# extensionboard.net
KiCad netlist of a schematic drawn in Altium Designer
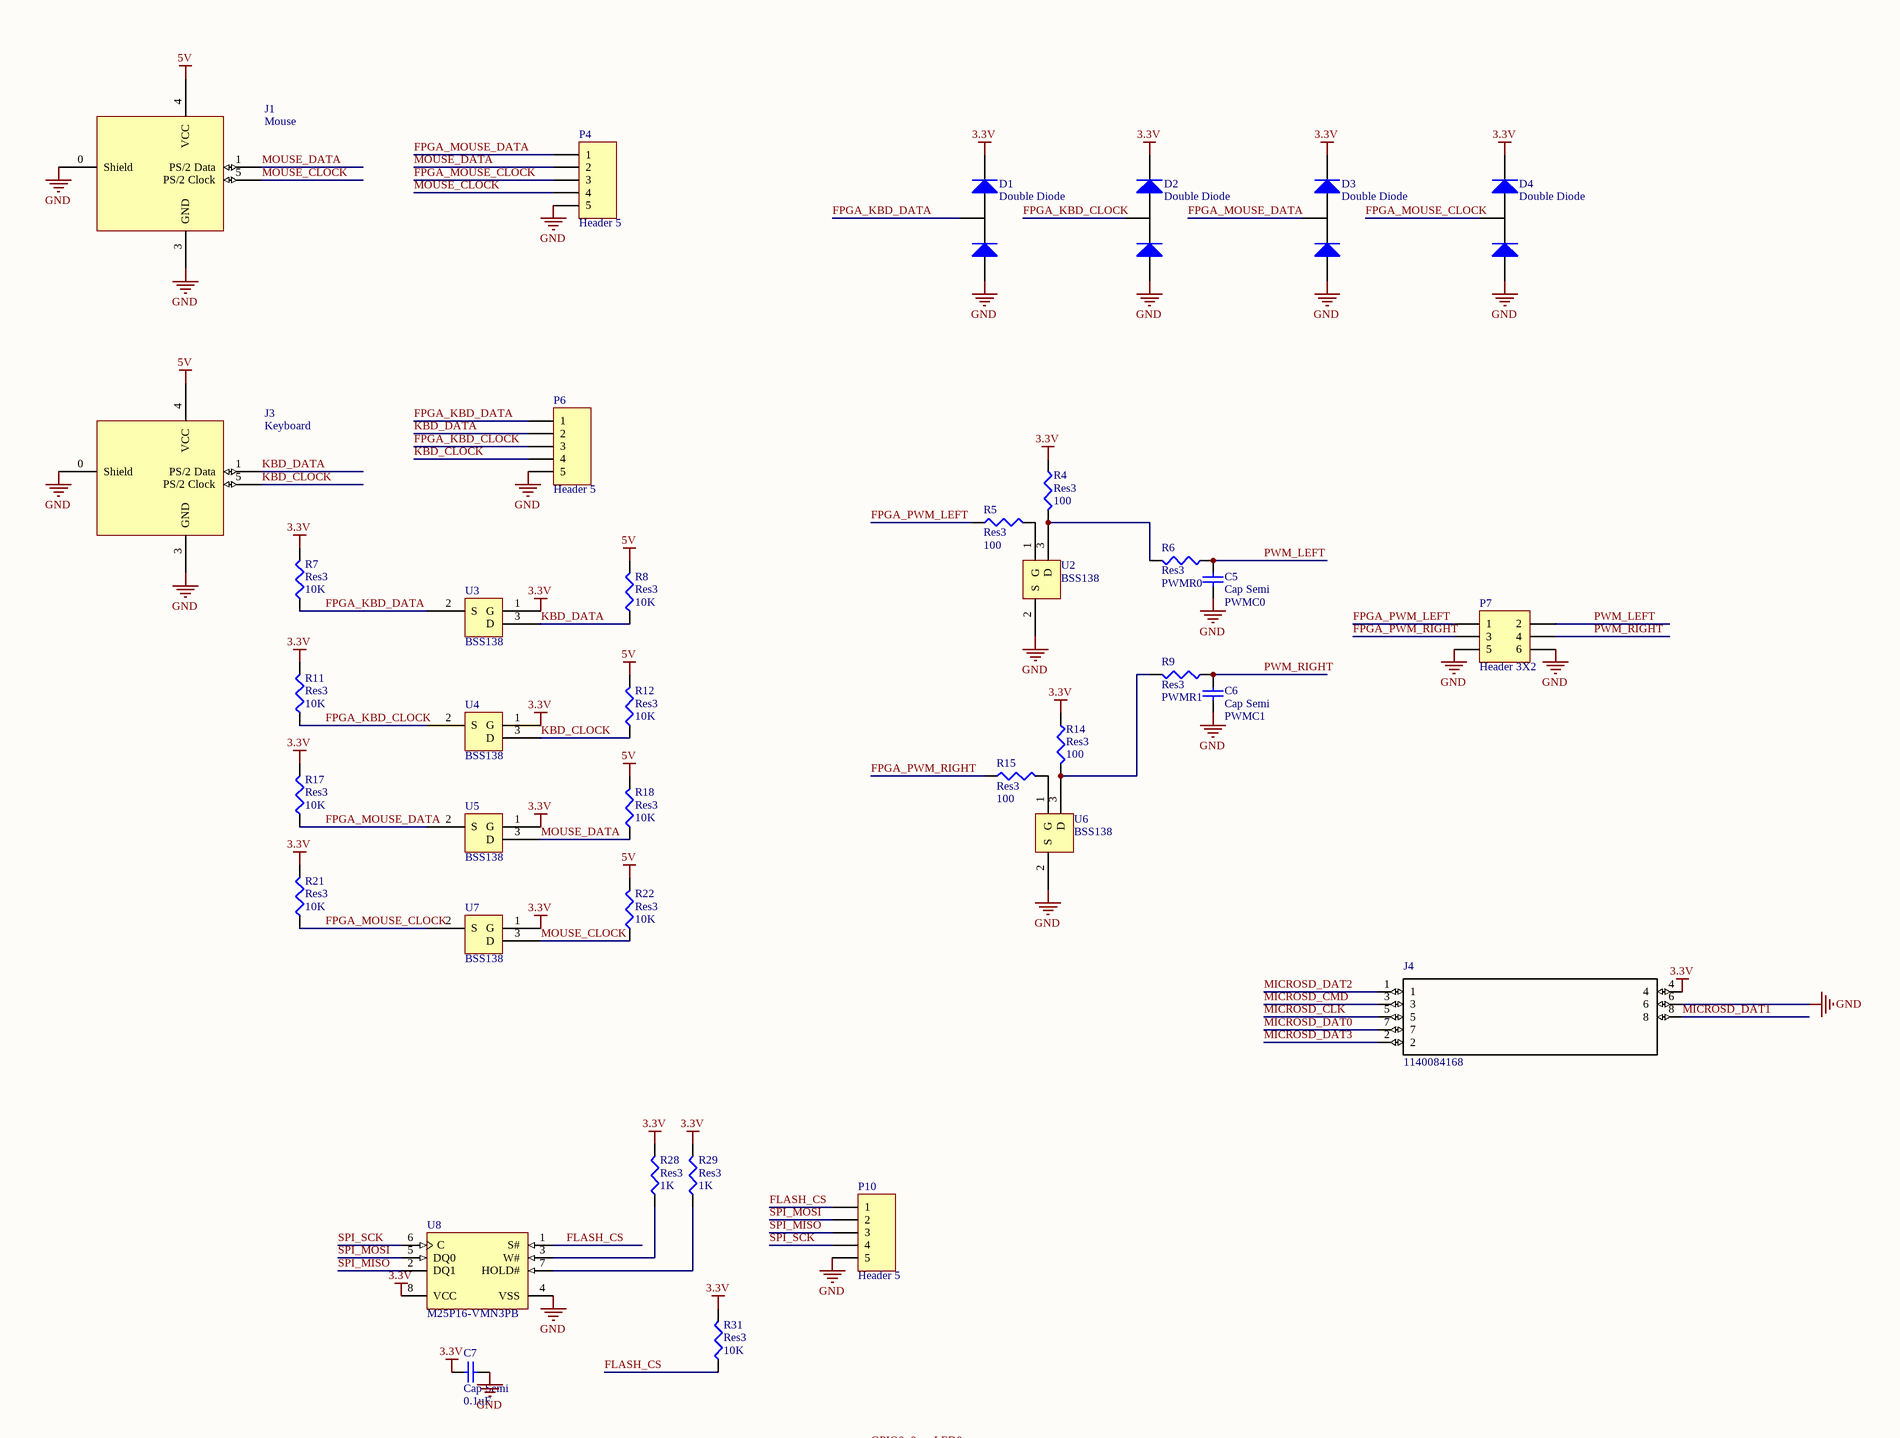
[diagram p0: extensionboard.SchDoc, top left]
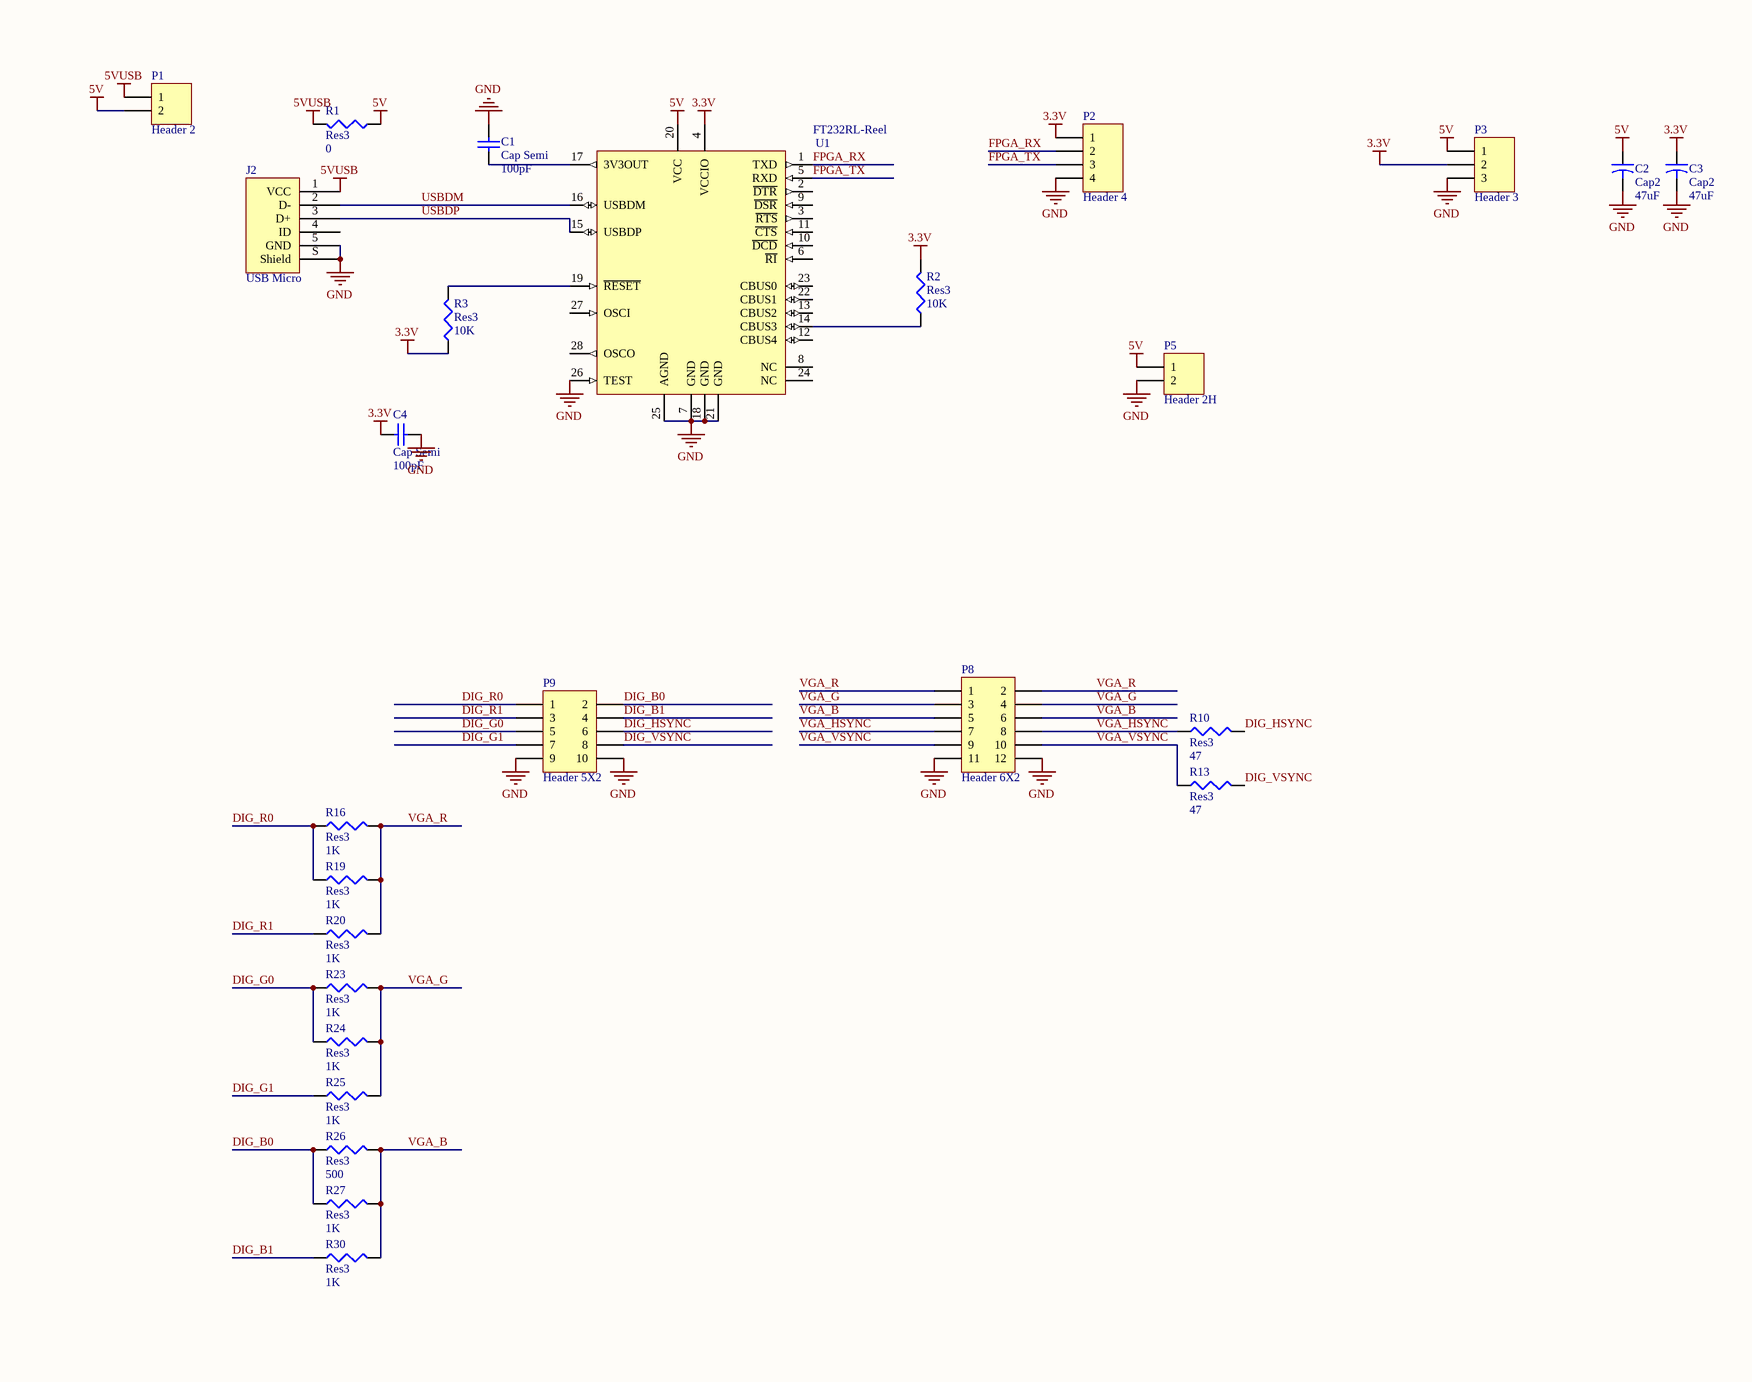
[diagram p1: extensionboard.SchDoc, top right]
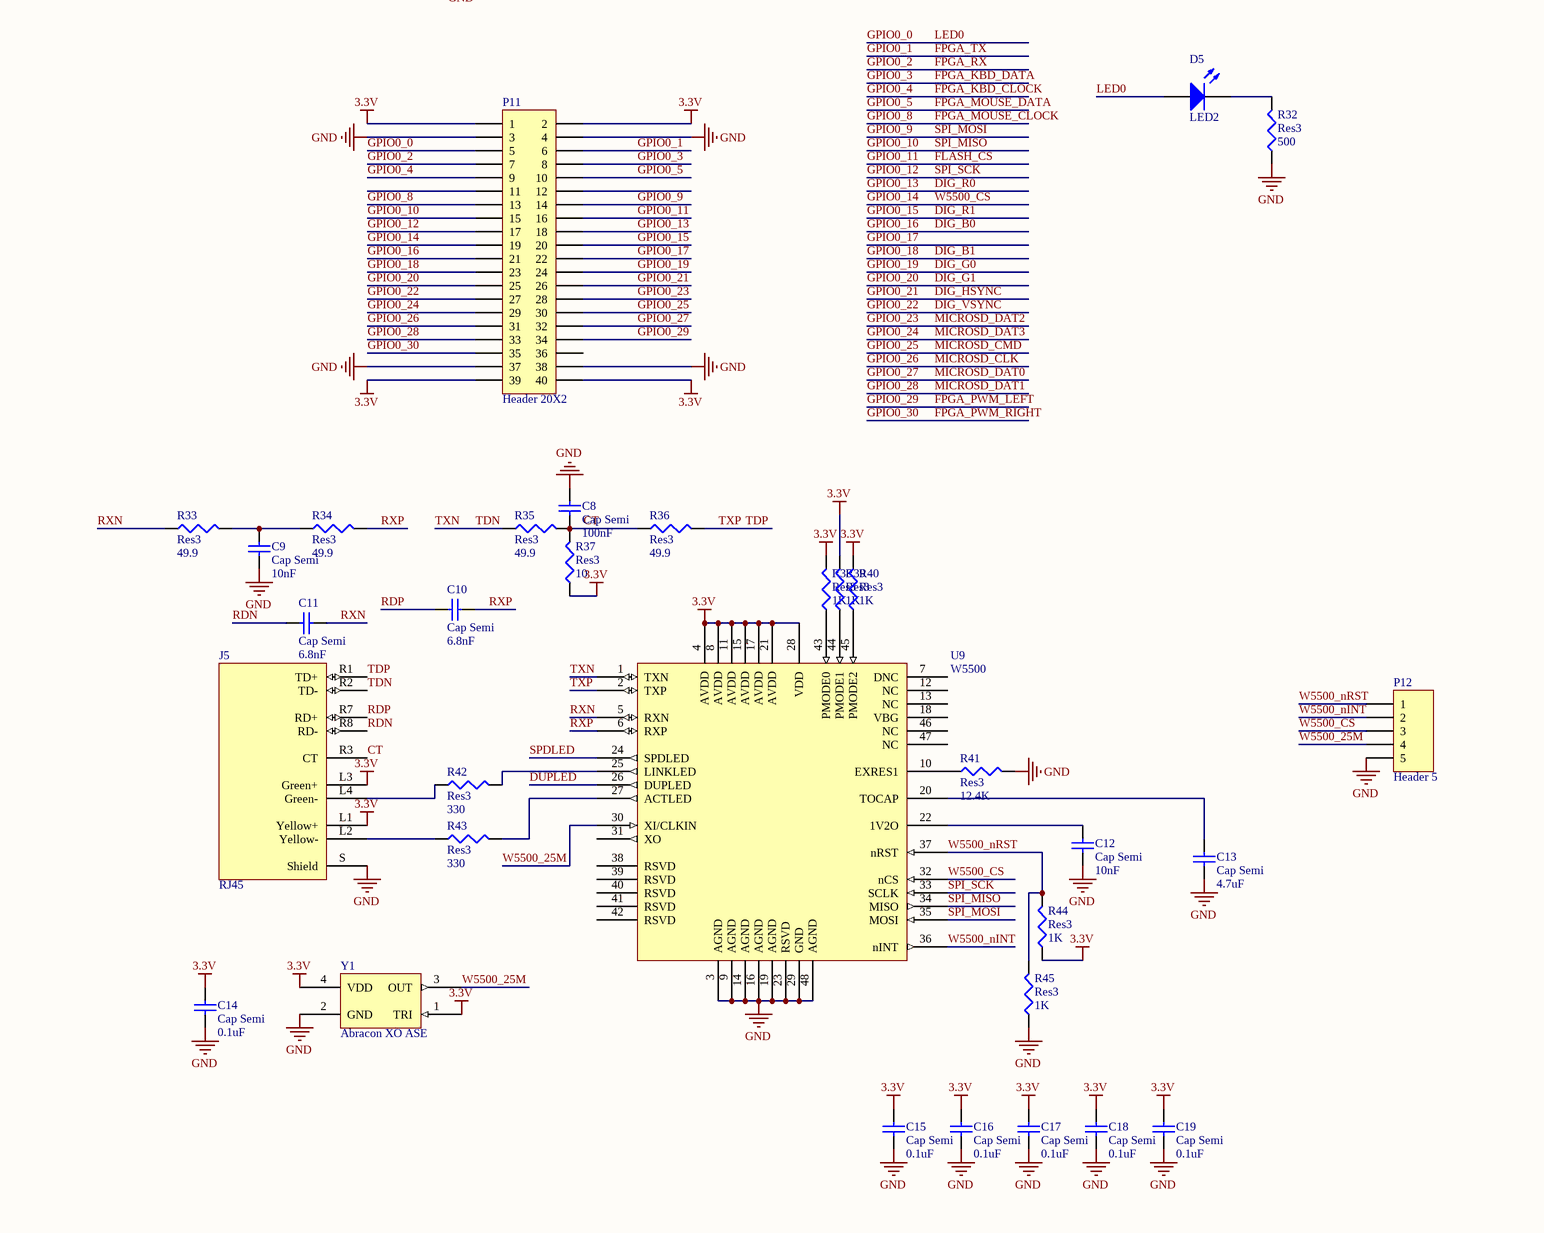
[diagram p2: extensionboard.SchDoc, bottom left]

(export (version "E")
  (design (tool "Eeschema 10.0.6"))
  (components
    (comp (ref "C1")
      (value "Cap Semi")
      (footprint "1608[0603]")
      (description "Capacitor (Semiconductor SIM Model)")
      (fields (field (name "ALTIUM_VALUE") "100pF") (field (name "PUBLISHER") "Altium Limited"))
      (libsource (lib "Miscellaneous Devices") (part "Cap Semi"))
    )
    (comp (ref "C2")
      (value "Cap2")
      (footprint "CAPR5-4X5")
      (description "Capacitor")
      (fields (field (name "ALTIUM_VALUE") "47uF") (field (name "PUBLISHER") "Altium Limited"))
      (libsource (lib "Miscellaneous Devices") (part "Cap2"))
    )
    (comp (ref "C3")
      (value "Cap2")
      (footprint "CAPR5-4X5")
      (description "Capacitor")
      (fields (field (name "ALTIUM_VALUE") "47uF") (field (name "PUBLISHER") "Altium Limited"))
      (libsource (lib "Miscellaneous Devices") (part "Cap2"))
    )
    (comp (ref "C4")
      (value "Cap Semi")
      (footprint "1608[0603]")
      (description "Capacitor (Semiconductor SIM Model)")
      (fields (field (name "ALTIUM_VALUE") "100pF") (field (name "PUBLISHER") "Altium Limited"))
      (libsource (lib "Miscellaneous Devices") (part "Cap Semi"))
    )
    (comp (ref "C5")
      (value "Cap Semi")
      (footprint "C1210")
      (description "Capacitor (Semiconductor SIM Model)")
      (fields (field (name "ALTIUM_VALUE") "PWMC0") (field (name "PUBLISHER") "Altium Limited"))
      (libsource (lib "Miscellaneous Devices") (part "Cap Semi"))
    )
    (comp (ref "C6")
      (value "Cap Semi")
      (footprint "C1210")
      (description "Capacitor (Semiconductor SIM Model)")
      (fields (field (name "ALTIUM_VALUE") "PWMC1") (field (name "PUBLISHER") "Altium Limited"))
      (libsource (lib "Miscellaneous Devices") (part "Cap Semi"))
    )
    (comp (ref "C7")
      (value "Cap Semi")
      (footprint "1608[0603]")
      (description "Capacitor (Semiconductor SIM Model)")
      (fields (field (name "ALTIUM_VALUE") "0.1uF") (field (name "PUBLISHER") "Altium Limited"))
      (libsource (lib "Miscellaneous Devices") (part "Cap Semi"))
    )
    (comp (ref "C8")
      (value "Cap Semi")
      (footprint "1608[0603]")
      (description "Capacitor (Semiconductor SIM Model)")
      (fields (field (name "ALTIUM_VALUE") "100nF") (field (name "PUBLISHER") "Altium Limited"))
      (libsource (lib "Miscellaneous Devices") (part "Cap Semi"))
    )
    (comp (ref "C9")
      (value "Cap Semi")
      (footprint "1608[0603]")
      (description "Capacitor (Semiconductor SIM Model)")
      (fields (field (name "ALTIUM_VALUE") "10nF") (field (name "PUBLISHER") "Altium Limited"))
      (libsource (lib "Miscellaneous Devices") (part "Cap Semi"))
    )
    (comp (ref "C10")
      (value "Cap Semi")
      (footprint "1608[0603]")
      (description "Capacitor (Semiconductor SIM Model)")
      (fields (field (name "ALTIUM_VALUE") "6.8nF") (field (name "PUBLISHER") "Altium Limited"))
      (libsource (lib "Miscellaneous Devices") (part "Cap Semi"))
    )
    (comp (ref "C11")
      (value "Cap Semi")
      (footprint "1608[0603]")
      (description "Capacitor (Semiconductor SIM Model)")
      (fields (field (name "ALTIUM_VALUE") "6.8nF") (field (name "PUBLISHER") "Altium Limited"))
      (libsource (lib "Miscellaneous Devices") (part "Cap Semi"))
    )
    (comp (ref "C12")
      (value "Cap Semi")
      (footprint "1608[0603]")
      (description "Capacitor (Semiconductor SIM Model)")
      (fields (field (name "ALTIUM_VALUE") "10nF") (field (name "PUBLISHER") "Altium Limited"))
      (libsource (lib "Miscellaneous Devices") (part "Cap Semi"))
    )
    (comp (ref "C13")
      (value "Cap Semi")
      (footprint "1608[0603]")
      (description "Capacitor (Semiconductor SIM Model)")
      (fields (field (name "ALTIUM_VALUE") "4.7uF") (field (name "PUBLISHER") "Altium Limited"))
      (libsource (lib "Miscellaneous Devices") (part "Cap Semi"))
    )
    (comp (ref "C14")
      (value "Cap Semi")
      (footprint "1608[0603]")
      (description "Capacitor (Semiconductor SIM Model)")
      (fields (field (name "ALTIUM_VALUE") "0.1uF") (field (name "PUBLISHER") "Altium Limited"))
      (libsource (lib "Miscellaneous Devices") (part "Cap Semi"))
    )
    (comp (ref "C15")
      (value "Cap Semi")
      (footprint "1608[0603]")
      (description "Capacitor (Semiconductor SIM Model)")
      (fields (field (name "ALTIUM_VALUE") "0.1uF") (field (name "PUBLISHER") "Altium Limited"))
      (libsource (lib "Miscellaneous Devices") (part "Cap Semi"))
    )
    (comp (ref "C16")
      (value "Cap Semi")
      (footprint "1608[0603]")
      (description "Capacitor (Semiconductor SIM Model)")
      (fields (field (name "ALTIUM_VALUE") "0.1uF") (field (name "PUBLISHER") "Altium Limited"))
      (libsource (lib "Miscellaneous Devices") (part "Cap Semi"))
    )
    (comp (ref "C17")
      (value "Cap Semi")
      (footprint "1608[0603]")
      (description "Capacitor (Semiconductor SIM Model)")
      (fields (field (name "ALTIUM_VALUE") "0.1uF") (field (name "PUBLISHER") "Altium Limited"))
      (libsource (lib "Miscellaneous Devices") (part "Cap Semi"))
    )
    (comp (ref "C18")
      (value "Cap Semi")
      (footprint "1608[0603]")
      (description "Capacitor (Semiconductor SIM Model)")
      (fields (field (name "ALTIUM_VALUE") "0.1uF") (field (name "PUBLISHER") "Altium Limited"))
      (libsource (lib "Miscellaneous Devices") (part "Cap Semi"))
    )
    (comp (ref "C19")
      (value "Cap Semi")
      (footprint "1608[0603]")
      (description "Capacitor (Semiconductor SIM Model)")
      (fields (field (name "ALTIUM_VALUE") "0.1uF") (field (name "PUBLISHER") "Altium Limited"))
      (libsource (lib "Miscellaneous Devices") (part "Cap Semi"))
    )
    (comp (ref "D1") (value "Double Diode") (footprint "SOT-23") (libsource (lib "BAT54S") (part "BAT54S")))
    (comp (ref "D2") (value "Double Diode") (footprint "SOT-23") (libsource (lib "BAT54S") (part "BAT54S")))
    (comp (ref "D3") (value "Double Diode") (footprint "SOT-23") (libsource (lib "BAT54S") (part "BAT54S")))
    (comp (ref "D4") (value "Double Diode") (footprint "SOT-23") (libsource (lib "BAT54S") (part "BAT54S")))
    (comp (ref "D5")
      (value "LED2")
      (footprint "3.2X1.6X1.1")
      (description "Typical RED, GREEN, YELLOW, AMBER GaAs LED")
      (fields (field (name "PUBLISHER") "Altium Limited"))
      (libsource (lib "Miscellaneous Devices") (part "LED2"))
    )
    (comp (ref "J1") (value "Mouse") (footprint "MD-60S") (libsource (lib "PSslash2") (part "MD60S")))
    (comp (ref "J2")
      (value "USB Micro")
      (footprint "FCI USB 10118193-0001LF")
      (libsource (lib "MicroUSB") (part "USB 2.0 Type B Micro"))
    )
    (comp (ref "J3") (value "Keyboard") (footprint "MD-60S") (libsource (lib "PSslash2") (part "MD60S")))
    (comp (ref "J4")
      (value "1140084168")
      (footprint "1140084168")
      (description "Memory Card Connector, Microsd, 8 Position, Full Reel")
      (fields (field (name "DIGI-KEY_PART_NUMBER") "114-00841-68-1-ND") (field (name "MF") "Amphenol ICC"))
      (libsource (lib "1140084168") (part "1140084168"))
    )
    (comp (ref "J5") (value "RJ45") (footprint "RB1-125BAG1A") (libsource (lib "MAGJACK RJ45") (part "RJ45")))
    (comp (ref "P1")
      (value "Header 2")
      (footprint "HDR1X2")
      (description "Header, 2-Pin")
      (fields (field (name "PUBLISHER") "Altium Limited"))
      (libsource (lib "Miscellaneous Connectors") (part "Header 2"))
    )
    (comp (ref "P2")
      (value "Header 4")
      (footprint "HDR1X4")
      (description "Header, 4-Pin")
      (fields (field (name "PUBLISHER") "Altium Limited"))
      (libsource (lib "Miscellaneous Connectors") (part "Header 4"))
    )
    (comp (ref "P3")
      (value "Header 3")
      (footprint "HDR1X3")
      (description "Header, 3-Pin")
      (fields (field (name "PUBLISHER") "Altium Limited"))
      (libsource (lib "Miscellaneous Connectors") (part "Header 3"))
    )
    (comp (ref "P4")
      (value "Header 5")
      (footprint "HDR1X5")
      (description "Header, 5-Pin")
      (fields (field (name "PUBLISHER") "Altium Limited"))
      (libsource (lib "Miscellaneous Connectors") (part "Header 5"))
    )
    (comp (ref "P5")
      (value "Header 2H")
      (footprint "HDR1X2H")
      (description "Header, 2-Pin, Right Angle")
      (fields (field (name "PUBLISHER") "Altium Limited"))
      (libsource (lib "Miscellaneous Connectors") (part "Header 2H"))
    )
    (comp (ref "P6")
      (value "Header 5")
      (footprint "HDR1X5")
      (description "Header, 5-Pin")
      (fields (field (name "PUBLISHER") "Altium Limited"))
      (libsource (lib "Miscellaneous Connectors") (part "Header 5"))
    )
    (comp (ref "P7")
      (value "Header 3X2")
      (footprint "HDR2X3")
      (description "Header, 3-Pin, Dual row")
      (fields (field (name "PUBLISHER") "Altium Limited"))
      (libsource (lib "Miscellaneous Connectors") (part "Header 3X2"))
    )
    (comp (ref "P8")
      (value "Header 6X2")
      (footprint "HDR2X6")
      (description "Header, 6-Pin, Dual row")
      (fields (field (name "PUBLISHER") "Altium Limited"))
      (libsource (lib "Miscellaneous Connectors") (part "Header 6X2"))
    )
    (comp (ref "P9")
      (value "Header 5X2")
      (footprint "HDR2X5")
      (description "Header, 5-Pin, Dual row")
      (fields (field (name "PUBLISHER") "Altium Limited"))
      (libsource (lib "Miscellaneous Connectors") (part "Header 5X2"))
    )
    (comp (ref "P10")
      (value "Header 5")
      (footprint "HDR1X5")
      (description "Header, 5-Pin")
      (fields (field (name "PUBLISHER") "Altium Limited"))
      (libsource (lib "Miscellaneous Connectors") (part "Header 5"))
    )
    (comp (ref "P11")
      (value "Header 20X2")
      (footprint "HDR2X20")
      (description "Header, 20-Pin, Dual row")
      (fields (field (name "PUBLISHER") "Altium Limited"))
      (libsource (lib "Miscellaneous Connectors") (part "Header 20X2"))
    )
    (comp (ref "P12")
      (value "Header 5")
      (footprint "HDR1X5")
      (description "Header, 5-Pin")
      (fields (field (name "PUBLISHER") "Altium Limited"))
      (libsource (lib "Miscellaneous Connectors") (part "Header 5"))
    )
    (comp (ref "R1")
      (value "Res3")
      (footprint "14-1210")
      (description "Resistor")
      (fields (field (name "ALTIUM_VALUE") "0") (field (name "PUBLISHER") "Altium Limited"))
      (libsource (lib "Miscellaneous Devices") (part "Res3"))
    )
    (comp (ref "R2")
      (value "Res3")
      (footprint "J1-0603")
      (description "Resistor")
      (fields (field (name "ALTIUM_VALUE") "10K") (field (name "PUBLISHER") "Altium Limited"))
      (libsource (lib "Miscellaneous Devices") (part "Res3"))
    )
    (comp (ref "R3")
      (value "Res3")
      (footprint "J1-0603")
      (description "Resistor")
      (fields (field (name "ALTIUM_VALUE") "10K") (field (name "PUBLISHER") "Altium Limited"))
      (libsource (lib "Miscellaneous Devices") (part "Res3"))
    )
    (comp (ref "R4")
      (value "Res3")
      (footprint "14-1210")
      (description "Resistor")
      (fields (field (name "ALTIUM_VALUE") "100") (field (name "PUBLISHER") "Altium Limited"))
      (libsource (lib "Miscellaneous Devices") (part "Res3"))
    )
    (comp (ref "R5")
      (value "Res3")
      (footprint "14-1210")
      (description "Resistor")
      (fields (field (name "ALTIUM_VALUE") "100") (field (name "PUBLISHER") "Altium Limited"))
      (libsource (lib "Miscellaneous Devices") (part "Res3"))
    )
    (comp (ref "R6")
      (value "Res3")
      (footprint "14-1210")
      (description "Resistor")
      (fields (field (name "ALTIUM_VALUE") "PWMR0") (field (name "PUBLISHER") "Altium Limited"))
      (libsource (lib "Miscellaneous Devices") (part "Res3"))
    )
    (comp (ref "R7")
      (value "Res3")
      (footprint "J1-0603")
      (description "Resistor")
      (fields (field (name "ALTIUM_VALUE") "10K") (field (name "PUBLISHER") "Altium Limited"))
      (libsource (lib "Miscellaneous Devices") (part "Res3"))
    )
    (comp (ref "R8")
      (value "Res3")
      (footprint "J1-0603")
      (description "Resistor")
      (fields (field (name "ALTIUM_VALUE") "10K") (field (name "PUBLISHER") "Altium Limited"))
      (libsource (lib "Miscellaneous Devices") (part "Res3"))
    )
    (comp (ref "R9")
      (value "Res3")
      (footprint "14-1210")
      (description "Resistor")
      (fields (field (name "ALTIUM_VALUE") "PWMR1") (field (name "PUBLISHER") "Altium Limited"))
      (libsource (lib "Miscellaneous Devices") (part "Res3"))
    )
    (comp (ref "R10")
      (value "Res3")
      (footprint "J1-0603")
      (description "Resistor")
      (fields (field (name "ALTIUM_VALUE") "47") (field (name "PUBLISHER") "Altium Limited"))
      (libsource (lib "Miscellaneous Devices") (part "Res3"))
    )
    (comp (ref "R11")
      (value "Res3")
      (footprint "J1-0603")
      (description "Resistor")
      (fields (field (name "ALTIUM_VALUE") "10K") (field (name "PUBLISHER") "Altium Limited"))
      (libsource (lib "Miscellaneous Devices") (part "Res3"))
    )
    (comp (ref "R12")
      (value "Res3")
      (footprint "J1-0603")
      (description "Resistor")
      (fields (field (name "ALTIUM_VALUE") "10K") (field (name "PUBLISHER") "Altium Limited"))
      (libsource (lib "Miscellaneous Devices") (part "Res3"))
    )
    (comp (ref "R13")
      (value "Res3")
      (footprint "J1-0603")
      (description "Resistor")
      (fields (field (name "ALTIUM_VALUE") "47") (field (name "PUBLISHER") "Altium Limited"))
      (libsource (lib "Miscellaneous Devices") (part "Res3"))
    )
    (comp (ref "R14")
      (value "Res3")
      (footprint "14-1210")
      (description "Resistor")
      (fields (field (name "ALTIUM_VALUE") "100") (field (name "PUBLISHER") "Altium Limited"))
      (libsource (lib "Miscellaneous Devices") (part "Res3"))
    )
    (comp (ref "R15")
      (value "Res3")
      (footprint "14-1210")
      (description "Resistor")
      (fields (field (name "ALTIUM_VALUE") "100") (field (name "PUBLISHER") "Altium Limited"))
      (libsource (lib "Miscellaneous Devices") (part "Res3"))
    )
    (comp (ref "R16")
      (value "Res3")
      (footprint "J1-0603")
      (description "Resistor")
      (fields (field (name "ALTIUM_VALUE") "1K") (field (name "PUBLISHER") "Altium Limited"))
      (libsource (lib "Miscellaneous Devices") (part "Res3"))
    )
    (comp (ref "R17")
      (value "Res3")
      (footprint "J1-0603")
      (description "Resistor")
      (fields (field (name "ALTIUM_VALUE") "10K") (field (name "PUBLISHER") "Altium Limited"))
      (libsource (lib "Miscellaneous Devices") (part "Res3"))
    )
    (comp (ref "R18")
      (value "Res3")
      (footprint "J1-0603")
      (description "Resistor")
      (fields (field (name "ALTIUM_VALUE") "10K") (field (name "PUBLISHER") "Altium Limited"))
      (libsource (lib "Miscellaneous Devices") (part "Res3"))
    )
    (comp (ref "R19")
      (value "Res3")
      (footprint "J1-0603")
      (description "Resistor")
      (fields (field (name "ALTIUM_VALUE") "1K") (field (name "PUBLISHER") "Altium Limited"))
      (libsource (lib "Miscellaneous Devices") (part "Res3"))
    )
    (comp (ref "R20")
      (value "Res3")
      (footprint "J1-0603")
      (description "Resistor")
      (fields (field (name "ALTIUM_VALUE") "1K") (field (name "PUBLISHER") "Altium Limited"))
      (libsource (lib "Miscellaneous Devices") (part "Res3"))
    )
    (comp (ref "R21")
      (value "Res3")
      (footprint "J1-0603")
      (description "Resistor")
      (fields (field (name "ALTIUM_VALUE") "10K") (field (name "PUBLISHER") "Altium Limited"))
      (libsource (lib "Miscellaneous Devices") (part "Res3"))
    )
    (comp (ref "R22")
      (value "Res3")
      (footprint "J1-0603")
      (description "Resistor")
      (fields (field (name "ALTIUM_VALUE") "10K") (field (name "PUBLISHER") "Altium Limited"))
      (libsource (lib "Miscellaneous Devices") (part "Res3"))
    )
    (comp (ref "R23")
      (value "Res3")
      (footprint "J1-0603")
      (description "Resistor")
      (fields (field (name "ALTIUM_VALUE") "1K") (field (name "PUBLISHER") "Altium Limited"))
      (libsource (lib "Miscellaneous Devices") (part "Res3"))
    )
    (comp (ref "R24")
      (value "Res3")
      (footprint "J1-0603")
      (description "Resistor")
      (fields (field (name "ALTIUM_VALUE") "1K") (field (name "PUBLISHER") "Altium Limited"))
      (libsource (lib "Miscellaneous Devices") (part "Res3"))
    )
    (comp (ref "R25")
      (value "Res3")
      (footprint "J1-0603")
      (description "Resistor")
      (fields (field (name "ALTIUM_VALUE") "1K") (field (name "PUBLISHER") "Altium Limited"))
      (libsource (lib "Miscellaneous Devices") (part "Res3"))
    )
    (comp (ref "R26")
      (value "Res3")
      (footprint "J1-0603")
      (description "Resistor")
      (fields (field (name "ALTIUM_VALUE") "500") (field (name "PUBLISHER") "Altium Limited"))
      (libsource (lib "Miscellaneous Devices") (part "Res3"))
    )
    (comp (ref "R27")
      (value "Res3")
      (footprint "J1-0603")
      (description "Resistor")
      (fields (field (name "ALTIUM_VALUE") "1K") (field (name "PUBLISHER") "Altium Limited"))
      (libsource (lib "Miscellaneous Devices") (part "Res3"))
    )
    (comp (ref "R28")
      (value "Res3")
      (footprint "J1-0603")
      (description "Resistor")
      (fields (field (name "ALTIUM_VALUE") "1K") (field (name "PUBLISHER") "Altium Limited"))
      (libsource (lib "Miscellaneous Devices") (part "Res3"))
    )
    (comp (ref "R29")
      (value "Res3")
      (footprint "J1-0603")
      (description "Resistor")
      (fields (field (name "ALTIUM_VALUE") "1K") (field (name "PUBLISHER") "Altium Limited"))
      (libsource (lib "Miscellaneous Devices") (part "Res3"))
    )
    (comp (ref "R30")
      (value "Res3")
      (footprint "J1-0603")
      (description "Resistor")
      (fields (field (name "ALTIUM_VALUE") "1K") (field (name "PUBLISHER") "Altium Limited"))
      (libsource (lib "Miscellaneous Devices") (part "Res3"))
    )
    (comp (ref "R31")
      (value "Res3")
      (footprint "J1-0603")
      (description "Resistor")
      (fields (field (name "ALTIUM_VALUE") "10K") (field (name "PUBLISHER") "Altium Limited"))
      (libsource (lib "Miscellaneous Devices") (part "Res3"))
    )
    (comp (ref "R32")
      (value "Res3")
      (footprint "J1-0603")
      (description "Resistor")
      (fields (field (name "ALTIUM_VALUE") "500") (field (name "PUBLISHER") "Altium Limited"))
      (libsource (lib "Miscellaneous Devices") (part "Res3"))
    )
    (comp (ref "R33")
      (value "Res3")
      (footprint "J1-0603")
      (description "Resistor")
      (fields (field (name "ALTIUM_VALUE") "49.9") (field (name "PUBLISHER") "Altium Limited"))
      (libsource (lib "Miscellaneous Devices") (part "Res3"))
    )
    (comp (ref "R34")
      (value "Res3")
      (footprint "J1-0603")
      (description "Resistor")
      (fields (field (name "ALTIUM_VALUE") "49.9") (field (name "PUBLISHER") "Altium Limited"))
      (libsource (lib "Miscellaneous Devices") (part "Res3"))
    )
    (comp (ref "R35")
      (value "Res3")
      (footprint "J1-0603")
      (description "Resistor")
      (fields (field (name "ALTIUM_VALUE") "49.9") (field (name "PUBLISHER") "Altium Limited"))
      (libsource (lib "Miscellaneous Devices") (part "Res3"))
    )
    (comp (ref "R36")
      (value "Res3")
      (footprint "J1-0603")
      (description "Resistor")
      (fields (field (name "ALTIUM_VALUE") "49.9") (field (name "PUBLISHER") "Altium Limited"))
      (libsource (lib "Miscellaneous Devices") (part "Res3"))
    )
    (comp (ref "R37")
      (value "Res3")
      (footprint "J1-0603")
      (description "Resistor")
      (fields (field (name "ALTIUM_VALUE") "10") (field (name "PUBLISHER") "Altium Limited"))
      (libsource (lib "Miscellaneous Devices") (part "Res3"))
    )
    (comp (ref "R38")
      (value "Res3")
      (footprint "J1-0603")
      (description "Resistor")
      (fields (field (name "ALTIUM_VALUE") "1K") (field (name "PUBLISHER") "Altium Limited"))
      (libsource (lib "Miscellaneous Devices") (part "Res3"))
    )
    (comp (ref "R39")
      (value "Res3")
      (footprint "J1-0603")
      (description "Resistor")
      (fields (field (name "ALTIUM_VALUE") "1K") (field (name "PUBLISHER") "Altium Limited"))
      (libsource (lib "Miscellaneous Devices") (part "Res3"))
    )
    (comp (ref "R40")
      (value "Res3")
      (footprint "J1-0603")
      (description "Resistor")
      (fields (field (name "ALTIUM_VALUE") "1K") (field (name "PUBLISHER") "Altium Limited"))
      (libsource (lib "Miscellaneous Devices") (part "Res3"))
    )
    (comp (ref "R41")
      (value "Res3")
      (footprint "J1-0603")
      (description "Resistor")
      (fields (field (name "ALTIUM_VALUE") "12.4K") (field (name "PUBLISHER") "Altium Limited"))
      (libsource (lib "Miscellaneous Devices") (part "Res3"))
    )
    (comp (ref "R42")
      (value "Res3")
      (footprint "J1-0603")
      (description "Resistor")
      (fields (field (name "ALTIUM_VALUE") "330") (field (name "PUBLISHER") "Altium Limited"))
      (libsource (lib "Miscellaneous Devices") (part "Res3"))
    )
    (comp (ref "R43")
      (value "Res3")
      (footprint "J1-0603")
      (description "Resistor")
      (fields (field (name "ALTIUM_VALUE") "330") (field (name "PUBLISHER") "Altium Limited"))
      (libsource (lib "Miscellaneous Devices") (part "Res3"))
    )
    (comp (ref "R44")
      (value "Res3")
      (footprint "J1-0603")
      (description "Resistor")
      (fields (field (name "ALTIUM_VALUE") "1K") (field (name "PUBLISHER") "Altium Limited"))
      (libsource (lib "Miscellaneous Devices") (part "Res3"))
    )
    (comp (ref "R45")
      (value "Res3")
      (footprint "J1-0603")
      (description "Resistor")
      (fields (field (name "ALTIUM_VALUE") "1K") (field (name "PUBLISHER") "Altium Limited"))
      (libsource (lib "Miscellaneous Devices") (part "Res3"))
    )
    (comp (ref "U1")
      (value "FT232RL-Reel")
      (footprint "SSOP-28_N")
      (description "USB UART Asynchronous Serial Data Transfer Chip, 28-pin SSOP, Tape and Reel")
      (fields (field (name "MANUFACTURER") "FTDI"))
      (libsource (lib "FTDI FT Series") (part "FT232RL-Reel"))
    )
    (comp (ref "U2")
      (value "BSS138")
      (footprint "SOT-23")
      (description "BSS138 SOT-23")
      (libsource (lib "BSS138") (part "BSS138"))
    )
    (comp (ref "U3")
      (value "BSS138")
      (footprint "SOT-23")
      (description "BSS138 SOT-23")
      (libsource (lib "") (part "BSS138_1"))
    )
    (comp (ref "U4")
      (value "BSS138")
      (footprint "SOT-23")
      (description "BSS138 SOT-23")
      (libsource (lib "") (part "BSS138_1"))
    )
    (comp (ref "U5")
      (value "BSS138")
      (footprint "SOT-23")
      (description "BSS138 SOT-23")
      (libsource (lib "") (part "BSS138_1"))
    )
    (comp (ref "U6")
      (value "BSS138")
      (footprint "SOT-23")
      (description "BSS138 SOT-23")
      (libsource (lib "BSS138") (part "BSS138"))
    )
    (comp (ref "U7")
      (value "BSS138")
      (footprint "SOT-23")
      (description "BSS138 SOT-23")
      (libsource (lib "") (part "BSS138_1"))
    )
    (comp (ref "U8")
      (value "M25P16-VMN3PB")
      (footprint "MICT-MN-8_N")
      (description "16 Mb (x1) Automotive Serial NOR Flash Memory, 75 MHz, 2.7 to 3.6 V, 8-pin SO8 Narrow (MN), Tube")
      (fields (field (name "VOLTAGE") "2.7V-3.6V ") (field (name "MANUFACTURER") "Micron"))
      (libsource (lib "Micron Memory Serial NOR Flash") (part "M25P16-VMN3PB"))
    )
    (comp (ref "U9")
      (value "W5500")
      (footprint "LQFP-48")
      (description "W5500 LQFP-48")
      (libsource (lib "W5500") (part "W5500"))
    )
    (comp (ref "Y1")
      (value "Abracon XO ASE")
      (footprint "ABRACON ASE")
      (description "SMD CMOS Crystal Oscillator")
      (libsource (lib "ABRACON ASE") (part "Abracon XO ASE"))
    )
  )
  (nets
    (net (code "1") (name "/CT") (class "Default")
      (node (ref "C8") (pin "2") (pinfunction "2_2") (pintype "passive"))
      (node (ref "J5") (pin "R3") (pinfunction "CT_R3") (pintype "passive"))
      (node (ref "R35") (pin "2") (pinfunction "2_2") (pintype "passive"))
      (node (ref "R36") (pin "1") (pinfunction "1_1") (pintype "passive"))
      (node (ref "R37") (pin "2") (pinfunction "2_2") (pintype "passive"))
    )
    (net (code "2") (name "/DIG_B0") (class "Default")
      (node (ref "P11") (pin "21") (pinfunction "21_21") (pintype "passive"))
      (node (ref "P9") (pin "2") (pinfunction "2_2") (pintype "passive"))
      (node (ref "R26") (pin "1") (pinfunction "1_1") (pintype "passive"))
      (node (ref "R27") (pin "1") (pinfunction "1_1") (pintype "passive"))
    )
    (net (code "3") (name "/DIG_B1") (class "Default")
      (node (ref "P11") (pin "23") (pinfunction "23_23") (pintype "passive"))
      (node (ref "P9") (pin "4") (pinfunction "4_4") (pintype "passive"))
      (node (ref "R30") (pin "1") (pinfunction "1_1") (pintype "passive"))
    )
    (net (code "4") (name "/DIG_G0") (class "Default")
      (node (ref "P11") (pin "24") (pinfunction "24_24") (pintype "passive"))
      (node (ref "P9") (pin "5") (pinfunction "5_5") (pintype "passive"))
      (node (ref "R23") (pin "1") (pinfunction "1_1") (pintype "passive"))
      (node (ref "R24") (pin "1") (pinfunction "1_1") (pintype "passive"))
    )
    (net (code "5") (name "/DIG_G1") (class "Default")
      (node (ref "P11") (pin "25") (pinfunction "25_25") (pintype "passive"))
      (node (ref "P9") (pin "7") (pinfunction "7_7") (pintype "passive"))
      (node (ref "R25") (pin "1") (pinfunction "1_1") (pintype "passive"))
    )
    (net (code "6") (name "/DIG_HSYNC") (class "Default")
      (node (ref "P11") (pin "26") (pinfunction "26_26") (pintype "passive"))
      (node (ref "P9") (pin "6") (pinfunction "6_6") (pintype "passive"))
      (node (ref "R10") (pin "2") (pinfunction "2_2") (pintype "passive"))
    )
    (net (code "7") (name "/DIG_R0") (class "Default")
      (node (ref "P11") (pin "18") (pinfunction "18_18") (pintype "passive"))
      (node (ref "P9") (pin "1") (pinfunction "1_1") (pintype "passive"))
      (node (ref "R16") (pin "1") (pinfunction "1_1") (pintype "passive"))
      (node (ref "R19") (pin "1") (pinfunction "1_1") (pintype "passive"))
    )
    (net (code "8") (name "/DIG_R1") (class "Default")
      (node (ref "P11") (pin "20") (pinfunction "20_20") (pintype "passive"))
      (node (ref "P9") (pin "3") (pinfunction "3_3") (pintype "passive"))
      (node (ref "R20") (pin "1") (pinfunction "1_1") (pintype "passive"))
    )
    (net (code "9") (name "/DIG_VSYNC") (class "Default")
      (node (ref "P11") (pin "27") (pinfunction "27_27") (pintype "passive"))
      (node (ref "P9") (pin "8") (pinfunction "8_8") (pintype "passive"))
      (node (ref "R13") (pin "2") (pinfunction "2_2") (pintype "passive"))
    )
    (net (code "10") (name "/DUPLED") (class "Default")
      (node (ref "U9") (pin "26") (pinfunction "DUPLED_26") (pintype "output"))
    )
    (net (code "11") (name "/FLASH_CS") (class "Default")
      (node (ref "P10") (pin "1") (pinfunction "1_1") (pintype "passive"))
      (node (ref "P11") (pin "16") (pinfunction "16_16") (pintype "passive"))
      (node (ref "R31") (pin "1") (pinfunction "1_1") (pintype "passive"))
      (node (ref "U8") (pin "1") (pinfunction "S#_1") (pintype "input"))
    )
    (net (code "12") (name "/FPGA_KBD_CLOCK") (class "Default")
      (node (ref "D2") (pin "3") (pintype "passive"))
      (node (ref "P11") (pin "9") (pinfunction "9_9") (pintype "passive"))
      (node (ref "P6") (pin "3") (pinfunction "3_3") (pintype "passive"))
      (node (ref "R11") (pin "1") (pinfunction "1_1") (pintype "passive"))
      (node (ref "U4") (pin "2") (pinfunction "S_2") (pintype "passive"))
    )
    (net (code "13") (name "/FPGA_KBD_DATA") (class "Default")
      (node (ref "D1") (pin "3") (pintype "passive"))
      (node (ref "P11") (pin "8") (pinfunction "8_8") (pintype "passive"))
      (node (ref "P6") (pin "1") (pinfunction "1_1") (pintype "passive"))
      (node (ref "R7") (pin "1") (pinfunction "1_1") (pintype "passive"))
      (node (ref "U3") (pin "2") (pinfunction "S_2") (pintype "passive"))
    )
    (net (code "14") (name "/FPGA_MOUSE_CLOCK") (class "Default")
      (node (ref "D4") (pin "3") (pintype "passive"))
      (node (ref "P11") (pin "13") (pinfunction "13_13") (pintype "passive"))
      (node (ref "P4") (pin "3") (pinfunction "3_3") (pintype "passive"))
      (node (ref "R21") (pin "1") (pinfunction "1_1") (pintype "passive"))
      (node (ref "U7") (pin "2") (pinfunction "S_2") (pintype "passive"))
    )
    (net (code "15") (name "/FPGA_MOUSE_DATA") (class "Default")
      (node (ref "D3") (pin "3") (pintype "passive"))
      (node (ref "P11") (pin "10") (pinfunction "10_10") (pintype "passive"))
      (node (ref "P4") (pin "1") (pinfunction "1_1") (pintype "passive"))
      (node (ref "R17") (pin "1") (pinfunction "1_1") (pintype "passive"))
      (node (ref "U5") (pin "2") (pinfunction "S_2") (pintype "passive"))
    )
    (net (code "16") (name "/FPGA_PWM_LEFT") (class "Default")
      (node (ref "P11") (pin "34") (pinfunction "34_34") (pintype "passive"))
      (node (ref "P7") (pin "1") (pinfunction "1_1") (pintype "passive"))
      (node (ref "R5") (pin "1") (pinfunction "1_1") (pintype "passive"))
    )
    (net (code "17") (name "/FPGA_PWM_RIGHT") (class "Default")
      (node (ref "P11") (pin "35") (pinfunction "35_35") (pintype "passive"))
      (node (ref "P7") (pin "3") (pinfunction "3_3") (pintype "passive"))
      (node (ref "R15") (pin "1") (pinfunction "1_1") (pintype "passive"))
    )
    (net (code "18") (name "/FPGA_RX") (class "Default")
      (node (ref "P11") (pin "7") (pinfunction "7_7") (pintype "passive"))
      (node (ref "P2") (pin "2") (pinfunction "2_2") (pintype "passive"))
      (node (ref "U1") (pin "1") (pinfunction "TXD_1") (pintype "output"))
    )
    (net (code "19") (name "/FPGA_TX") (class "Default")
      (node (ref "P11") (pin "6") (pinfunction "6_6") (pintype "passive"))
      (node (ref "P2") (pin "3") (pinfunction "3_3") (pintype "passive"))
      (node (ref "U1") (pin "5") (pinfunction "RXD_5") (pintype "input"))
    )
    (net (code "20") (name "/GPIO0_0") (class "Default")
      (node (ref "D5") (pin "1") (pinfunction "A_1") (pintype "passive"))
      (node (ref "P11") (pin "5") (pinfunction "5_5") (pintype "passive"))
    )
    (net (code "21") (name "/GPIO0_9") (class "Default")
      (node (ref "P10") (pin "2") (pinfunction "2_2") (pintype "passive"))
      (node (ref "P11") (pin "14") (pinfunction "14_14") (pintype "passive"))
      (node (ref "U8") (pin "5") (pinfunction "DQ0_5") (pintype "input"))
      (node (ref "U9") (pin "35") (pinfunction "MOSI_35") (pintype "input"))
    )
    (net (code "22") (name "/GPIO0_10") (class "Default")
      (node (ref "P10") (pin "3") (pinfunction "3_3") (pintype "passive"))
      (node (ref "P11") (pin "15") (pinfunction "15_15") (pintype "passive"))
      (node (ref "U8") (pin "2") (pinfunction "DQ1_2") (pintype "tri_state"))
      (node (ref "U9") (pin "34") (pinfunction "MISO_34") (pintype "output"))
    )
    (net (code "23") (name "/GPIO0_12") (class "Default")
      (node (ref "P10") (pin "4") (pinfunction "4_4") (pintype "passive"))
      (node (ref "P11") (pin "17") (pinfunction "17_17") (pintype "passive"))
      (node (ref "U8") (pin "6") (pinfunction "C_6") (pintype "input"))
      (node (ref "U9") (pin "33") (pinfunction "SCLK_33") (pintype "input"))
    )
    (net (code "24") (name "/GPIO0_14") (class "Default")
      (node (ref "P11") (pin "19") (pinfunction "19_19") (pintype "passive"))
      (node (ref "P12") (pin "3") (pinfunction "3_3") (pintype "passive"))
      (node (ref "U9") (pin "32") (pinfunction "nCS_32") (pintype "input"))
    )
    (net (code "25") (name "/GPIO0_17") (class "Default")
      (node (ref "P11") (pin "22") (pinfunction "22_22") (pintype "passive"))
    )
    (net (code "26") (name "/GPIO0_23") (class "Default")
      (node (ref "J4") (pin "1") (pinfunction "1_1") (pintype "bidirectional"))
      (node (ref "P11") (pin "28") (pinfunction "28_28") (pintype "passive"))
    )
    (net (code "27") (name "/GPIO0_24") (class "Default")
      (node (ref "J4") (pin "2") (pinfunction "2_2") (pintype "bidirectional"))
      (node (ref "P11") (pin "29") (pinfunction "29_29") (pintype "passive"))
    )
    (net (code "28") (name "/GPIO0_25") (class "Default")
      (node (ref "J4") (pin "3") (pinfunction "3_3") (pintype "bidirectional"))
      (node (ref "P11") (pin "30") (pinfunction "30_30") (pintype "passive"))
    )
    (net (code "29") (name "/GPIO0_26") (class "Default")
      (node (ref "J4") (pin "5") (pinfunction "5_5") (pintype "bidirectional"))
      (node (ref "P11") (pin "31") (pinfunction "31_31") (pintype "passive"))
    )
    (net (code "30") (name "/GPIO0_27") (class "Default")
      (node (ref "J4") (pin "7") (pinfunction "7_7") (pintype "bidirectional"))
      (node (ref "P11") (pin "32") (pinfunction "32_32") (pintype "passive"))
    )
    (net (code "31") (name "/GPIO0_28") (class "Default")
      (node (ref "J4") (pin "8") (pinfunction "8_8") (pintype "bidirectional"))
      (node (ref "P11") (pin "33") (pinfunction "33_33") (pintype "passive"))
    )
    (net (code "32") (name "/KBD_CLOCK") (class "Default")
      (node (ref "J3") (pin "5") (pinfunction "PS/2_Clock_5") (pintype "bidirectional"))
      (node (ref "P6") (pin "4") (pinfunction "4_4") (pintype "passive"))
      (node (ref "R12") (pin "1") (pinfunction "1_1") (pintype "passive"))
      (node (ref "U4") (pin "3") (pinfunction "D_3") (pintype "passive"))
    )
    (net (code "33") (name "/KBD_DATA") (class "Default")
      (node (ref "J3") (pin "1") (pinfunction "PS/2_Data_1") (pintype "bidirectional"))
      (node (ref "P6") (pin "2") (pinfunction "2_2") (pintype "passive"))
      (node (ref "R8") (pin "1") (pinfunction "1_1") (pintype "passive"))
      (node (ref "U3") (pin "3") (pinfunction "D_3") (pintype "passive"))
    )
    (net (code "34") (name "/MOUSE_CLOCK") (class "Default")
      (node (ref "J1") (pin "5") (pinfunction "PS/2_Clock_5") (pintype "bidirectional"))
      (node (ref "P4") (pin "4") (pinfunction "4_4") (pintype "passive"))
      (node (ref "R22") (pin "1") (pinfunction "1_1") (pintype "passive"))
      (node (ref "U7") (pin "3") (pinfunction "D_3") (pintype "passive"))
    )
    (net (code "35") (name "/MOUSE_DATA") (class "Default")
      (node (ref "J1") (pin "1") (pinfunction "PS/2_Data_1") (pintype "bidirectional"))
      (node (ref "P4") (pin "2") (pinfunction "2_2") (pintype "passive"))
      (node (ref "R18") (pin "1") (pinfunction "1_1") (pintype "passive"))
      (node (ref "U5") (pin "3") (pinfunction "D_3") (pintype "passive"))
    )
    (net (code "36") (name "/PWM_LEFT") (class "Default")
      (node (ref "C5") (pin "2") (pinfunction "2_2") (pintype "passive"))
      (node (ref "P7") (pin "2") (pinfunction "2_2") (pintype "passive"))
      (node (ref "R6") (pin "1") (pinfunction "1_1") (pintype "passive"))
    )
    (net (code "37") (name "/PWM_RIGHT") (class "Default")
      (node (ref "C6") (pin "2") (pinfunction "2_2") (pintype "passive"))
      (node (ref "P7") (pin "4") (pinfunction "4_4") (pintype "passive"))
      (node (ref "R9") (pin "1") (pinfunction "1_1") (pintype "passive"))
    )
    (net (code "38") (name "/RDN") (class "Default")
      (node (ref "C11") (pin "1") (pinfunction "1_1") (pintype "passive"))
      (node (ref "J5") (pin "R8") (pinfunction "RD-_R8") (pintype "bidirectional"))
    )
    (net (code "39") (name "/RDP") (class "Default")
      (node (ref "C10") (pin "1") (pinfunction "1_1") (pintype "passive"))
      (node (ref "J5") (pin "R7") (pinfunction "RD+_R7") (pintype "bidirectional"))
    )
    (net (code "40") (name "/RXN") (class "Default")
      (node (ref "C11") (pin "2") (pinfunction "2_2") (pintype "passive"))
      (node (ref "R33") (pin "1") (pinfunction "1_1") (pintype "passive"))
      (node (ref "U9") (pin "5") (pinfunction "RXN_5") (pintype "bidirectional"))
    )
    (net (code "41") (name "/RXP") (class "Default")
      (node (ref "C10") (pin "2") (pinfunction "2_2") (pintype "passive"))
      (node (ref "R34") (pin "2") (pinfunction "2_2") (pintype "passive"))
      (node (ref "U9") (pin "6") (pinfunction "RXP_6") (pintype "bidirectional"))
    )
    (net (code "42") (name "/SPDLED") (class "Default")
      (node (ref "U9") (pin "24") (pinfunction "SPDLED_24") (pintype "output"))
    )
    (net (code "43") (name "/TDN") (class "Default")
      (node (ref "J5") (pin "R2") (pinfunction "TD-_R2") (pintype "bidirectional"))
      (node (ref "R35") (pin "1") (pinfunction "1_1") (pintype "passive"))
      (node (ref "U9") (pin "1") (pinfunction "TXN_1") (pintype "bidirectional"))
    )
    (net (code "44") (name "/TDP") (class "Default")
      (node (ref "J5") (pin "R1") (pinfunction "TD+_R1") (pintype "bidirectional"))
      (node (ref "R36") (pin "2") (pinfunction "2_2") (pintype "passive"))
      (node (ref "U9") (pin "2") (pinfunction "TXP_2") (pintype "bidirectional"))
    )
    (net (code "45") (name "/USBDM") (class "Default")
      (node (ref "J2") (pin "2") (pinfunction "D-_2") (pintype "passive"))
      (node (ref "U1") (pin "16") (pinfunction "USBDM_16") (pintype "bidirectional"))
    )
    (net (code "46") (name "/USBDP") (class "Default")
      (node (ref "J2") (pin "3") (pinfunction "D+_3") (pintype "passive"))
      (node (ref "U1") (pin "15") (pinfunction "USBDP_15") (pintype "bidirectional"))
    )
    (net (code "47") (name "/VGA_B") (class "Default")
      (node (ref "P8") (pin "5") (pinfunction "5_5") (pintype "passive"))
      (node (ref "P8") (pin "6") (pinfunction "6_6") (pintype "passive"))
      (node (ref "R26") (pin "2") (pinfunction "2_2") (pintype "passive"))
      (node (ref "R27") (pin "2") (pinfunction "2_2") (pintype "passive"))
      (node (ref "R30") (pin "2") (pinfunction "2_2") (pintype "passive"))
    )
    (net (code "48") (name "/VGA_G") (class "Default")
      (node (ref "P8") (pin "3") (pinfunction "3_3") (pintype "passive"))
      (node (ref "P8") (pin "4") (pinfunction "4_4") (pintype "passive"))
      (node (ref "R23") (pin "2") (pinfunction "2_2") (pintype "passive"))
      (node (ref "R24") (pin "2") (pinfunction "2_2") (pintype "passive"))
      (node (ref "R25") (pin "2") (pinfunction "2_2") (pintype "passive"))
    )
    (net (code "49") (name "/VGA_HSYNC") (class "Default")
      (node (ref "P8") (pin "7") (pinfunction "7_7") (pintype "passive"))
      (node (ref "P8") (pin "8") (pinfunction "8_8") (pintype "passive"))
      (node (ref "R10") (pin "1") (pinfunction "1_1") (pintype "passive"))
    )
    (net (code "50") (name "/VGA_R") (class "Default")
      (node (ref "P8") (pin "1") (pinfunction "1_1") (pintype "passive"))
      (node (ref "P8") (pin "2") (pinfunction "2_2") (pintype "passive"))
      (node (ref "R16") (pin "2") (pinfunction "2_2") (pintype "passive"))
      (node (ref "R19") (pin "2") (pinfunction "2_2") (pintype "passive"))
      (node (ref "R20") (pin "2") (pinfunction "2_2") (pintype "passive"))
    )
    (net (code "51") (name "/VGA_VSYNC") (class "Default")
      (node (ref "P8") (pin "10") (pinfunction "10_10") (pintype "passive"))
      (node (ref "P8") (pin "9") (pinfunction "9_9") (pintype "passive"))
      (node (ref "R13") (pin "1") (pinfunction "1_1") (pintype "passive"))
    )
    (net (code "52") (name "/W5500_25M") (class "Default")
      (node (ref "P12") (pin "4") (pinfunction "4_4") (pintype "passive"))
      (node (ref "U9") (pin "30") (pinfunction "XI/CLKIN_30") (pintype "input"))
      (node (ref "Y1") (pin "3") (pinfunction "OUT_3") (pintype "output"))
    )
    (net (code "53") (name "/W5500_nINT") (class "Default")
      (node (ref "P12") (pin "2") (pinfunction "2_2") (pintype "passive"))
      (node (ref "U9") (pin "36") (pinfunction "nINT_36") (pintype "output"))
    )
    (net (code "54") (name "/W5500_nRST") (class "Default")
      (node (ref "P12") (pin "1") (pinfunction "1_1") (pintype "passive"))
      (node (ref "R44") (pin "2") (pinfunction "2_2") (pintype "passive"))
      (node (ref "R45") (pin "2") (pinfunction "2_2") (pintype "passive"))
      (node (ref "U9") (pin "37") (pinfunction "nRST_37") (pintype "input"))
    )
    (net (code "55") (name "3.3V") (class "Default")
      (node (ref "C14") (pin "2") (pinfunction "2_2") (pintype "passive"))
      (node (ref "C15") (pin "2") (pinfunction "2_2") (pintype "passive"))
      (node (ref "C16") (pin "2") (pinfunction "2_2") (pintype "passive"))
      (node (ref "C17") (pin "2") (pinfunction "2_2") (pintype "passive"))
      (node (ref "C18") (pin "2") (pinfunction "2_2") (pintype "passive"))
      (node (ref "C19") (pin "2") (pinfunction "2_2") (pintype "passive"))
      (node (ref "C3") (pin "1") (pinfunction "1_1") (pintype "passive"))
      (node (ref "C4") (pin "1") (pinfunction "1_1") (pintype "passive"))
      (node (ref "C7") (pin "1") (pinfunction "1_1") (pintype "passive"))
      (node (ref "D1") (pin "2") (pintype "passive"))
      (node (ref "D2") (pin "2") (pintype "passive"))
      (node (ref "D3") (pin "2") (pintype "passive"))
      (node (ref "D4") (pin "2") (pintype "passive"))
      (node (ref "J4") (pin "4") (pinfunction "4_4") (pintype "bidirectional"))
      (node (ref "J5") (pin "L1") (pinfunction "Yellow+_L1") (pintype "passive"))
      (node (ref "J5") (pin "L3") (pinfunction "Green+_L3") (pintype "passive"))
      (node (ref "P11") (pin "1") (pinfunction "1_1") (pintype "passive"))
      (node (ref "P11") (pin "2") (pinfunction "2_2") (pintype "passive"))
      (node (ref "P11") (pin "39") (pinfunction "39_39") (pintype "passive"))
      (node (ref "P11") (pin "40") (pinfunction "40_40") (pintype "passive"))
      (node (ref "P2") (pin "1") (pinfunction "1_1") (pintype "passive"))
      (node (ref "P3") (pin "2") (pinfunction "2_2") (pintype "passive"))
      (node (ref "R11") (pin "2") (pinfunction "2_2") (pintype "passive"))
      (node (ref "R14") (pin "1") (pinfunction "1_1") (pintype "passive"))
      (node (ref "R17") (pin "2") (pinfunction "2_2") (pintype "passive"))
      (node (ref "R2") (pin "2") (pinfunction "2_2") (pintype "passive"))
      (node (ref "R21") (pin "2") (pinfunction "2_2") (pintype "passive"))
      (node (ref "R28") (pin "2") (pinfunction "2_2") (pintype "passive"))
      (node (ref "R29") (pin "2") (pinfunction "2_2") (pintype "passive"))
      (node (ref "R3") (pin "1") (pinfunction "1_1") (pintype "passive"))
      (node (ref "R31") (pin "2") (pinfunction "2_2") (pintype "passive"))
      (node (ref "R37") (pin "1") (pinfunction "1_1") (pintype "passive"))
      (node (ref "R38") (pin "2") (pinfunction "2_2") (pintype "passive"))
      (node (ref "R39") (pin "2") (pinfunction "2_2") (pintype "passive"))
      (node (ref "R4") (pin "1") (pinfunction "1_1") (pintype "passive"))
      (node (ref "R40") (pin "2") (pinfunction "2_2") (pintype "passive"))
      (node (ref "R44") (pin "1") (pinfunction "1_1") (pintype "passive"))
      (node (ref "R7") (pin "2") (pinfunction "2_2") (pintype "passive"))
      (node (ref "U1") (pin "4") (pinfunction "VCCIO_4") (pintype "power_in"))
      (node (ref "U3") (pin "1") (pinfunction "G_1") (pintype "passive"))
      (node (ref "U4") (pin "1") (pinfunction "G_1") (pintype "passive"))
      (node (ref "U5") (pin "1") (pinfunction "G_1") (pintype "passive"))
      (node (ref "U7") (pin "1") (pinfunction "G_1") (pintype "passive"))
      (node (ref "U8") (pin "8") (pinfunction "VCC_8") (pintype "power_in"))
      (node (ref "U9") (pin "11") (pinfunction "AVDD_11") (pintype "power_in"))
      (node (ref "U9") (pin "15") (pinfunction "AVDD_15") (pintype "power_in"))
      (node (ref "U9") (pin "17") (pinfunction "AVDD_17") (pintype "power_in"))
      (node (ref "U9") (pin "21") (pinfunction "AVDD_21") (pintype "power_in"))
      (node (ref "U9") (pin "28") (pinfunction "VDD_28") (pintype "power_in"))
      (node (ref "U9") (pin "4") (pinfunction "AVDD_4") (pintype "power_in"))
      (node (ref "U9") (pin "8") (pinfunction "AVDD_8") (pintype "power_in"))
      (node (ref "Y1") (pin "1") (pinfunction "TRI_1") (pintype "input"))
      (node (ref "Y1") (pin "4") (pinfunction "VDD_4") (pintype "power_in"))
    )
    (net (code "56") (name "5V") (class "Default")
      (node (ref "C2") (pin "1") (pinfunction "1_1") (pintype "passive"))
      (node (ref "J1") (pin "4") (pinfunction "VCC_4") (pintype "power_in"))
      (node (ref "J3") (pin "4") (pinfunction "VCC_4") (pintype "power_in"))
      (node (ref "P1") (pin "2") (pinfunction "2_2") (pintype "passive"))
      (node (ref "P3") (pin "1") (pinfunction "1_1") (pintype "passive"))
      (node (ref "P5") (pin "1") (pinfunction "1_1") (pintype "passive"))
      (node (ref "R1") (pin "1") (pinfunction "1_1") (pintype "passive"))
      (node (ref "R12") (pin "2") (pinfunction "2_2") (pintype "passive"))
      (node (ref "R18") (pin "2") (pinfunction "2_2") (pintype "passive"))
      (node (ref "R22") (pin "2") (pinfunction "2_2") (pintype "passive"))
      (node (ref "R8") (pin "2") (pinfunction "2_2") (pintype "passive"))
      (node (ref "U1") (pin "20") (pinfunction "VCC_20") (pintype "power_in"))
    )
    (net (code "57") (name "5VUSB") (class "Default")
      (node (ref "J2") (pin "1") (pinfunction "VCC_1") (pintype "passive"))
      (node (ref "P1") (pin "1") (pinfunction "1_1") (pintype "passive"))
      (node (ref "R1") (pin "2") (pinfunction "2_2") (pintype "passive"))
    )
    (net (code "58") (name "GND") (class "Default")
      (node (ref "C1") (pin "2") (pinfunction "2_2") (pintype "passive"))
      (node (ref "C12") (pin "1") (pinfunction "1_1") (pintype "passive"))
      (node (ref "C13") (pin "1") (pinfunction "1_1") (pintype "passive"))
      (node (ref "C14") (pin "1") (pinfunction "1_1") (pintype "passive"))
      (node (ref "C15") (pin "1") (pinfunction "1_1") (pintype "passive"))
      (node (ref "C16") (pin "1") (pinfunction "1_1") (pintype "passive"))
      (node (ref "C17") (pin "1") (pinfunction "1_1") (pintype "passive"))
      (node (ref "C18") (pin "1") (pinfunction "1_1") (pintype "passive"))
      (node (ref "C19") (pin "1") (pinfunction "1_1") (pintype "passive"))
      (node (ref "C2") (pin "2") (pinfunction "2_2") (pintype "passive"))
      (node (ref "C3") (pin "2") (pinfunction "2_2") (pintype "passive"))
      (node (ref "C4") (pin "2") (pinfunction "2_2") (pintype "passive"))
      (node (ref "C5") (pin "1") (pinfunction "1_1") (pintype "passive"))
      (node (ref "C6") (pin "1") (pinfunction "1_1") (pintype "passive"))
      (node (ref "C7") (pin "2") (pinfunction "2_2") (pintype "passive"))
      (node (ref "C8") (pin "1") (pinfunction "1_1") (pintype "passive"))
      (node (ref "C9") (pin "2") (pinfunction "2_2") (pintype "passive"))
      (node (ref "D1") (pin "1") (pintype "passive"))
      (node (ref "D2") (pin "1") (pintype "passive"))
      (node (ref "D3") (pin "1") (pintype "passive"))
      (node (ref "D4") (pin "1") (pintype "passive"))
      (node (ref "J1") (pin "0") (pinfunction "Shield_0") (pintype "passive"))
      (node (ref "J1") (pin "3") (pinfunction "GND_3") (pintype "power_in"))
      (node (ref "J2") (pin "5") (pinfunction "GND_5") (pintype "passive"))
      (node (ref "J2") (pin "S") (pinfunction "Shield_S") (pintype "passive"))
      (node (ref "J3") (pin "0") (pinfunction "Shield_0") (pintype "passive"))
      (node (ref "J3") (pin "3") (pinfunction "GND_3") (pintype "power_in"))
      (node (ref "J4") (pin "6") (pinfunction "6_6") (pintype "bidirectional"))
      (node (ref "J5") (pin "S") (pinfunction "Shield_S") (pintype "passive"))
      (node (ref "P10") (pin "5") (pinfunction "5_5") (pintype "passive"))
      (node (ref "P11") (pin "3") (pinfunction "3_3") (pintype "passive"))
      (node (ref "P11") (pin "37") (pinfunction "37_37") (pintype "passive"))
      (node (ref "P11") (pin "38") (pinfunction "38_38") (pintype "passive"))
      (node (ref "P11") (pin "4") (pinfunction "4_4") (pintype "passive"))
      (node (ref "P12") (pin "5") (pinfunction "5_5") (pintype "passive"))
      (node (ref "P2") (pin "4") (pinfunction "4_4") (pintype "passive"))
      (node (ref "P3") (pin "3") (pinfunction "3_3") (pintype "passive"))
      (node (ref "P4") (pin "5") (pinfunction "5_5") (pintype "passive"))
      (node (ref "P5") (pin "2") (pinfunction "2_2") (pintype "passive"))
      (node (ref "P6") (pin "5") (pinfunction "5_5") (pintype "passive"))
      (node (ref "P7") (pin "5") (pinfunction "5_5") (pintype "passive"))
      (node (ref "P7") (pin "6") (pinfunction "6_6") (pintype "passive"))
      (node (ref "P8") (pin "11") (pinfunction "11_11") (pintype "passive"))
      (node (ref "P8") (pin "12") (pinfunction "12_12") (pintype "passive"))
      (node (ref "P9") (pin "10") (pinfunction "10_10") (pintype "passive"))
      (node (ref "P9") (pin "9") (pinfunction "9_9") (pintype "passive"))
      (node (ref "R32") (pin "1") (pinfunction "1_1") (pintype "passive"))
      (node (ref "R41") (pin "2") (pinfunction "2_2") (pintype "passive"))
      (node (ref "R45") (pin "1") (pinfunction "1_1") (pintype "passive"))
      (node (ref "U1") (pin "18") (pinfunction "GND_18") (pintype "power_in"))
      (node (ref "U1") (pin "21") (pinfunction "GND_21") (pintype "power_in"))
      (node (ref "U1") (pin "25") (pinfunction "AGND_25") (pintype "power_in"))
      (node (ref "U1") (pin "26") (pinfunction "TEST_26") (pintype "input"))
      (node (ref "U1") (pin "7") (pinfunction "GND_7") (pintype "power_in"))
      (node (ref "U2") (pin "2") (pinfunction "S_2") (pintype "passive"))
      (node (ref "U6") (pin "2") (pinfunction "S_2") (pintype "passive"))
      (node (ref "U8") (pin "4") (pinfunction "VSS_4") (pintype "power_in"))
      (node (ref "U9") (pin "14") (pinfunction "AGND_14") (pintype "power_in"))
      (node (ref "U9") (pin "16") (pinfunction "AGND_16") (pintype "power_in"))
      (node (ref "U9") (pin "19") (pinfunction "AGND_19") (pintype "power_in"))
      (node (ref "U9") (pin "23") (pinfunction "RSVD_23") (pintype "power_in"))
      (node (ref "U9") (pin "29") (pinfunction "GND_29") (pintype "power_in"))
      (node (ref "U9") (pin "3") (pinfunction "AGND_3") (pintype "power_in"))
      (node (ref "U9") (pin "48") (pinfunction "AGND_48") (pintype "power_in"))
      (node (ref "U9") (pin "9") (pinfunction "AGND_9") (pintype "power_in"))
      (node (ref "Y1") (pin "2") (pinfunction "GND_2") (pintype "power_in"))
    )
    (net (code "59") (name "Net-(C9-Pad1)") (class "Default")
      (node (ref "C9") (pin "1") (pinfunction "1_1") (pintype "passive"))
      (node (ref "R33") (pin "2") (pinfunction "2_2") (pintype "passive"))
      (node (ref "R34") (pin "1") (pinfunction "1_1") (pintype "passive"))
    )
    (net (code "60") (name "Net-(D5-K)") (class "Default")
      (node (ref "D5") (pin "2") (pinfunction "K_2") (pintype "passive"))
      (node (ref "R32") (pin "2") (pinfunction "2_2") (pintype "passive"))
    )
    (net (code "61") (name "Net-(J5-Green-)") (class "Default")
      (node (ref "J5") (pin "L4") (pinfunction "Green-_L4") (pintype "passive"))
      (node (ref "R42") (pin "1") (pinfunction "1_1") (pintype "passive"))
    )
    (net (code "62") (name "Net-(J5-Yellow-)") (class "Default")
      (node (ref "J5") (pin "L2") (pinfunction "Yellow-_L2") (pintype "passive"))
      (node (ref "R43") (pin "1") (pinfunction "1_1") (pintype "passive"))
    )
    (net (code "63") (name "Net-(U1-3V3OUT)") (class "Default")
      (node (ref "C1") (pin "1") (pinfunction "1_1") (pintype "passive"))
      (node (ref "U1") (pin "17") (pinfunction "3V3OUT_17") (pintype "output"))
    )
    (net (code "64") (name "Net-(U1-CBUS3)") (class "Default")
      (node (ref "R2") (pin "1") (pinfunction "1_1") (pintype "passive"))
      (node (ref "U1") (pin "14") (pinfunction "CBUS3_14") (pintype "bidirectional"))
    )
    (net (code "65") (name "Net-(U1-~{RESET})") (class "Default")
      (node (ref "R3") (pin "2") (pinfunction "2_2") (pintype "passive"))
      (node (ref "U1") (pin "19") (pinfunction "~{RESET}_19") (pintype "input"))
    )
    (net (code "66") (name "Net-(U2-D)") (class "Default")
      (node (ref "R4") (pin "2") (pinfunction "2_2") (pintype "passive"))
      (node (ref "R6") (pin "2") (pinfunction "2_2") (pintype "passive"))
      (node (ref "U2") (pin "3") (pinfunction "D_3") (pintype "passive"))
    )
    (net (code "67") (name "Net-(U2-G)") (class "Default")
      (node (ref "R5") (pin "2") (pinfunction "2_2") (pintype "passive"))
      (node (ref "U2") (pin "1") (pinfunction "G_1") (pintype "passive"))
    )
    (net (code "68") (name "Net-(U6-D)") (class "Default")
      (node (ref "R14") (pin "2") (pinfunction "2_2") (pintype "passive"))
      (node (ref "R9") (pin "2") (pinfunction "2_2") (pintype "passive"))
      (node (ref "U6") (pin "3") (pinfunction "D_3") (pintype "passive"))
    )
    (net (code "69") (name "Net-(U6-G)") (class "Default")
      (node (ref "R15") (pin "2") (pinfunction "2_2") (pintype "passive"))
      (node (ref "U6") (pin "1") (pinfunction "G_1") (pintype "passive"))
    )
    (net (code "70") (name "Net-(U8-HOLD#)") (class "Default")
      (node (ref "R29") (pin "1") (pinfunction "1_1") (pintype "passive"))
      (node (ref "U8") (pin "7") (pinfunction "HOLD#_7") (pintype "input"))
    )
    (net (code "71") (name "Net-(U8-W#)") (class "Default")
      (node (ref "R28") (pin "1") (pinfunction "1_1") (pintype "passive"))
      (node (ref "U8") (pin "3") (pinfunction "W#_3") (pintype "input"))
    )
    (net (code "72") (name "Net-(U9-1V2O)") (class "Default")
      (node (ref "C12") (pin "2") (pinfunction "2_2") (pintype "passive"))
      (node (ref "U9") (pin "22") (pinfunction "1V2O_22") (pintype "power_in"))
    )
    (net (code "73") (name "Net-(U9-ACTLED)") (class "Default")
      (node (ref "R43") (pin "2") (pinfunction "2_2") (pintype "passive"))
      (node (ref "U9") (pin "27") (pinfunction "ACTLED_27") (pintype "output"))
    )
    (net (code "74") (name "Net-(U9-EXRES1)") (class "Default")
      (node (ref "R41") (pin "1") (pinfunction "1_1") (pintype "passive"))
      (node (ref "U9") (pin "10") (pinfunction "EXRES1_10") (pintype "passive"))
    )
    (net (code "75") (name "Net-(U9-LINKLED)") (class "Default")
      (node (ref "R42") (pin "2") (pinfunction "2_2") (pintype "passive"))
      (node (ref "U9") (pin "25") (pinfunction "LINKLED_25") (pintype "output"))
    )
    (net (code "76") (name "Net-(U9-PMODE0)") (class "Default")
      (node (ref "R38") (pin "1") (pinfunction "1_1") (pintype "passive"))
      (node (ref "U9") (pin "43") (pinfunction "PMODE0_43") (pintype "input"))
    )
    (net (code "77") (name "Net-(U9-PMODE1)") (class "Default")
      (node (ref "R39") (pin "1") (pinfunction "1_1") (pintype "passive"))
      (node (ref "U9") (pin "44") (pinfunction "PMODE1_44") (pintype "input"))
    )
    (net (code "78") (name "Net-(U9-PMODE2)") (class "Default")
      (node (ref "R40") (pin "1") (pinfunction "1_1") (pintype "passive"))
      (node (ref "U9") (pin "45") (pinfunction "PMODE2_45") (pintype "input"))
    )
    (net (code "79") (name "Net-(U9-TOCAP)") (class "Default")
      (node (ref "C13") (pin "2") (pinfunction "2_2") (pintype "passive"))
      (node (ref "U9") (pin "20") (pinfunction "TOCAP_20") (pintype "passive"))
    )
    (net (code "80") (name "unconnected-(J2-ID-Pad4)") (class "Default")
      (node (ref "J2") (pin "4") (pinfunction "ID_4") (pintype "passive"))
    )
    (net (code "81") (name "unconnected-(P11-Pad11)") (class "Default")
      (node (ref "P11") (pin "11") (pinfunction "11_11") (pintype "passive"))
    )
    (net (code "82") (name "unconnected-(P11-Pad12)") (class "Default")
      (node (ref "P11") (pin "12") (pinfunction "12_12") (pintype "passive"))
    )
    (net (code "83") (name "unconnected-(P11-Pad36)") (class "Default")
      (node (ref "P11") (pin "36") (pinfunction "36_36") (pintype "passive"))
    )
    (net (code "84") (name "unconnected-(U1-CBUS0-Pad23)") (class "Default")
      (node (ref "U1") (pin "23") (pinfunction "CBUS0_23") (pintype "bidirectional"))
    )
    (net (code "85") (name "unconnected-(U1-CBUS1-Pad22)") (class "Default")
      (node (ref "U1") (pin "22") (pinfunction "CBUS1_22") (pintype "bidirectional"))
    )
    (net (code "86") (name "unconnected-(U1-CBUS2-Pad13)") (class "Default")
      (node (ref "U1") (pin "13") (pinfunction "CBUS2_13") (pintype "bidirectional"))
    )
    (net (code "87") (name "unconnected-(U1-CBUS4-Pad12)") (class "Default")
      (node (ref "U1") (pin "12") (pinfunction "CBUS4_12") (pintype "bidirectional"))
    )
    (net (code "88") (name "unconnected-(U1-NC-Pad8)") (class "Default")
      (node (ref "U1") (pin "8") (pinfunction "NC_8") (pintype "passive"))
    )
    (net (code "89") (name "unconnected-(U1-NC-Pad24)") (class "Default")
      (node (ref "U1") (pin "24") (pinfunction "NC_24") (pintype "passive"))
    )
    (net (code "90") (name "unconnected-(U1-OSCI-Pad27)") (class "Default")
      (node (ref "U1") (pin "27") (pinfunction "OSCI_27") (pintype "input"))
    )
    (net (code "91") (name "unconnected-(U1-OSCO-Pad28)") (class "Default")
      (node (ref "U1") (pin "28") (pinfunction "OSCO_28") (pintype "output"))
    )
    (net (code "92") (name "unconnected-(U1-~{CTS}-Pad11)") (class "Default")
      (node (ref "U1") (pin "11") (pinfunction "~{CTS}_11") (pintype "input"))
    )
    (net (code "93") (name "unconnected-(U1-~{DCD}-Pad10)") (class "Default")
      (node (ref "U1") (pin "10") (pinfunction "~{DCD}_10") (pintype "input"))
    )
    (net (code "94") (name "unconnected-(U1-~{DSR}-Pad9)") (class "Default")
      (node (ref "U1") (pin "9") (pinfunction "~{DSR}_9") (pintype "input"))
    )
    (net (code "95") (name "unconnected-(U1-~{DTR}-Pad2)") (class "Default")
      (node (ref "U1") (pin "2") (pinfunction "~{DTR}_2") (pintype "output"))
    )
    (net (code "96") (name "unconnected-(U1-~{RI}-Pad6)") (class "Default")
      (node (ref "U1") (pin "6") (pinfunction "~{RI}_6") (pintype "input"))
    )
    (net (code "97") (name "unconnected-(U1-~{RTS}-Pad3)") (class "Default")
      (node (ref "U1") (pin "3") (pinfunction "~{RTS}_3") (pintype "output"))
    )
    (net (code "98") (name "unconnected-(U9-DNC-Pad7)") (class "Default")
      (node (ref "U9") (pin "7") (pinfunction "DNC_7") (pintype "passive"))
    )
    (net (code "99") (name "unconnected-(U9-NC-Pad12)") (class "Default")
      (node (ref "U9") (pin "12") (pinfunction "NC_12") (pintype "passive"))
    )
    (net (code "100") (name "unconnected-(U9-NC-Pad13)") (class "Default")
      (node (ref "U9") (pin "13") (pinfunction "NC_13") (pintype "passive"))
    )
    (net (code "101") (name "unconnected-(U9-NC-Pad46)") (class "Default")
      (node (ref "U9") (pin "46") (pinfunction "NC_46") (pintype "power_in"))
    )
    (net (code "102") (name "unconnected-(U9-NC-Pad47)") (class "Default")
      (node (ref "U9") (pin "47") (pinfunction "NC_47") (pintype "power_in"))
    )
    (net (code "103") (name "unconnected-(U9-RSVD-Pad38)") (class "Default")
      (node (ref "U9") (pin "38") (pinfunction "RSVD_38") (pintype "power_in"))
    )
    (net (code "104") (name "unconnected-(U9-RSVD-Pad39)") (class "Default")
      (node (ref "U9") (pin "39") (pinfunction "RSVD_39") (pintype "power_in"))
    )
    (net (code "105") (name "unconnected-(U9-RSVD-Pad40)") (class "Default")
      (node (ref "U9") (pin "40") (pinfunction "RSVD_40") (pintype "power_in"))
    )
    (net (code "106") (name "unconnected-(U9-RSVD-Pad41)") (class "Default")
      (node (ref "U9") (pin "41") (pinfunction "RSVD_41") (pintype "power_in"))
    )
    (net (code "107") (name "unconnected-(U9-RSVD-Pad42)") (class "Default")
      (node (ref "U9") (pin "42") (pinfunction "RSVD_42") (pintype "power_in"))
    )
    (net (code "108") (name "unconnected-(U9-VBG-Pad18)") (class "Default")
      (node (ref "U9") (pin "18") (pinfunction "VBG_18") (pintype "passive"))
    )
    (net (code "109") (name "unconnected-(U9-XO-Pad31)") (class "Default")
      (node (ref "U9") (pin "31") (pinfunction "XO_31") (pintype "output"))
    )
  )
)
